# H01R0_Backend.net
KiCad netlist of a schematic drawn in Altium Designer
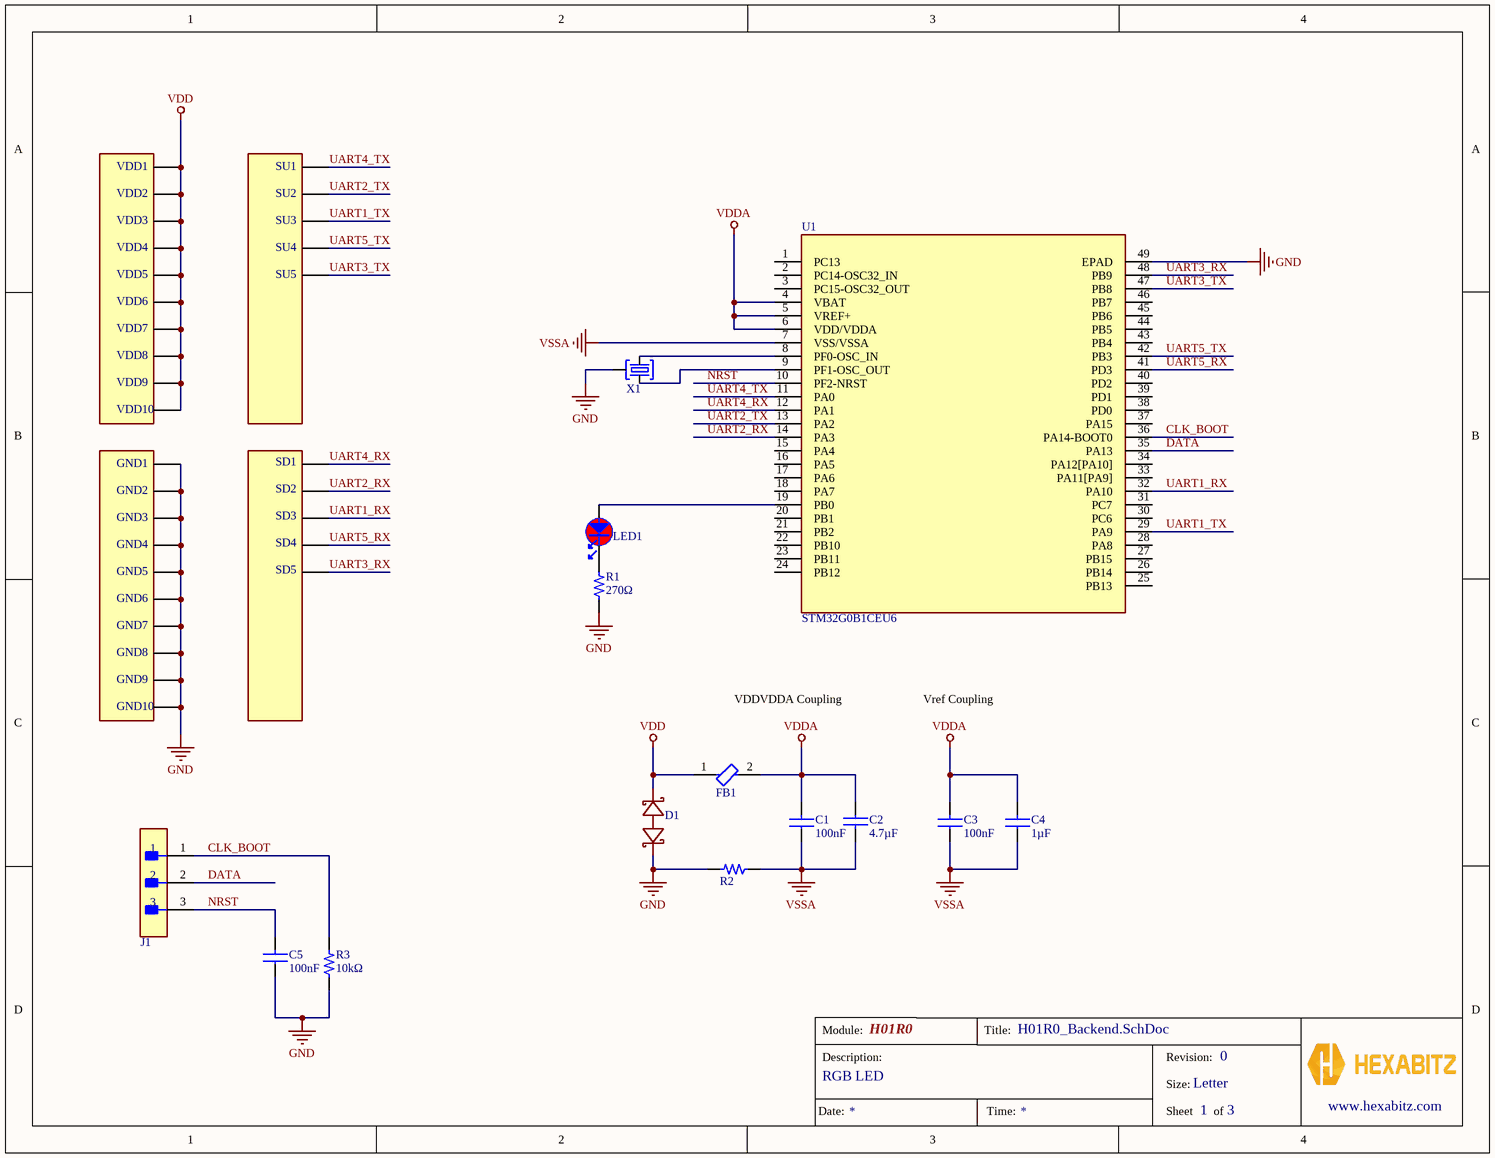
[diagram p0: H01R0_Backend.SchDoc]

(export (version "E")
  (design (tool "Eeschema 10.0.6"))
  (components
    (comp (ref "C1")
      (value "100nF")
      (footprint "C0603")
      (fields
        (field (name "MANUFACTURER") "Samsung Electro-Mechanics")
        (field (name "MANUFACTURER PART NUMBER") "CL10B104KA8NNNC")
        (field (name "TOLERANCE") "10%")
      )
      (libsource (lib "Hexabitz Altium Library") (part "generic Capacitor"))
    )
    (comp (ref "C2")
      (value "4.7µF")
      (footprint "C0805")
      (fields
        (field (name "MANUFACTURER") "Samsung Electro-Mechanics")
        (field (name "MANUFACTURER PART NUMBER") "CL21X475KAQNNNE")
        (field (name "TOLERANCE") "10%")
      )
      (libsource (lib "Hexabitz Altium Library") (part "generic Capacitor"))
    )
    (comp (ref "C3")
      (value "100nF")
      (footprint "C0603")
      (fields
        (field (name "MANUFACTURER") "Samsung Electro-Mechanics")
        (field (name "MANUFACTURER PART NUMBER") "CL10B104KA8NNNC")
        (field (name "TOLERANCE") "10%")
      )
      (libsource (lib "Hexabitz Altium Library") (part "generic Capacitor"))
    )
    (comp (ref "C4")
      (value "1µF")
      (footprint "C0805")
      (description "Ceramic Capacitor, Ceramic, 16V, 10% +Tol, 10% -Tol, X7R, 15% TC, 1uF, Surface Mount, 0805")
      (fields
        (field (name "MANUFACTURER") "Yageo Group")
        (field (name "MANUFACTURER PART NUMBER") "CC0805KKX7R7BB105")
      )
      (libsource (lib "Hexabitz Altium Library") (part "generic Capacitor"))
    )
    (comp (ref "C5")
      (value "100nF")
      (footprint "C0603")
      (fields
        (field (name "MANUFACTURER") "Samsung Electro-Mechanics")
        (field (name "MANUFACTURER PART NUMBER") "CL10B104KA8NNNC")
        (field (name "TOLERANCE") "10%")
      )
      (libsource (lib "Hexabitz Altium Library") (part "generic Capacitor"))
    )
    (comp (ref "D1")
      (value "CDSOD323-T03SC")
      (footprint "SOD2513X114N")
      (description "A 3V, 350W, bi-directional, standard capacitance, SOD323 pkg TVS Diode ¦ Bourns CDSOD323-T03SC")
      (fields (field (name "MANUFACTURER") "Bourns"))
      (libsource (lib "Hexabitz Altium Library") (part "CDSOD323-T03SC"))
    )
    (comp (ref "FB1")
      (value "MMZ1608Y300B")
      (footprint "FP-MMZ1608-0_8-MFG")
      (description "Ferrite Beads 0603 30ohms 1500mA Signal Line AEC-Q200")
      (fields
        (field (name "MANUFACTURER") "TDK")
        (field (name "MANUFACTURER PART NUMBER") "MMZ1608Y300BTD25")
      )
      (libsource (lib "Hexabitz Altium Library") (part "MMZ1608Y300B"))
    )
    (comp (ref "GND1")
      (value "HEXABIT_UART_PORT")
      (footprint "HEXABIT_POWER_PORT_D")
      (libsource (lib "hexabitz_connectors.Library") (part "HEXABIT_POWER_PORT_D"))
    )
    (comp (ref "GND2")
      (value "HEXABIT_UART_PORT")
      (footprint "HEXABIT_POWER_PORT_D")
      (libsource (lib "hexabitz_connectors.Library") (part "HEXABIT_POWER_PORT_D"))
    )
    (comp (ref "GND3")
      (value "HEXABIT_UART_PORT")
      (footprint "HEXABIT_POWER_PORT_D_300R")
      (libsource (lib "hexabitz_connectors.Library") (part "HEXABIT_POWER_PORT_D_300R"))
    )
    (comp (ref "GND4")
      (value "HEXABIT_UART_PORT")
      (footprint "HEXABIT_POWER_PORT_D")
      (libsource (lib "hexabitz_connectors.Library") (part "HEXABIT_POWER_PORT_D"))
    )
    (comp (ref "GND5")
      (value "HEXABIT_UART_PORT")
      (footprint "HEXABIT_POWER_PORT_D")
      (libsource (lib "hexabitz_connectors.Library") (part "HEXABIT_POWER_PORT_D"))
    )
    (comp (ref "GND6")
      (value "HEXABIT_UART_PORT")
      (footprint "HEXABIT_POWER_PORT_D")
      (libsource (lib "hexabitz_connectors.Library") (part "HEXABIT_POWER_PORT_D"))
    )
    (comp (ref "GND7")
      (value "HEXABIT_UART_PORT")
      (footprint "HEXABIT_POWER_PORT_D")
      (libsource (lib "hexabitz_connectors.Library") (part "HEXABIT_POWER_PORT_D"))
    )
    (comp (ref "GND8")
      (value "HEXABIT_UART_PORT")
      (footprint "HEXABIT_POWER_PORT_D_300L")
      (libsource (lib "hexabitz_connectors.Library") (part "HEXABIT_POWER_PORT_D_300L"))
    )
    (comp (ref "GND9")
      (value "HEXABIT_UART_PORT")
      (footprint "HEXABIT_POWER_PORT_D")
      (libsource (lib "hexabitz_connectors.Library") (part "HEXABIT_POWER_PORT_D"))
    )
    (comp (ref "GND10")
      (value "HEXABIT_UART_PORT")
      (footprint "HEXABIT_POWER_PORT_D")
      (libsource (lib "hexabitz_connectors.Library") (part "HEXABIT_POWER_PORT_D"))
    )
    (comp (ref "J1")
      (value "TSW-103-14-G-S")
      (footprint "FP-TSW-103-14-G-S-MFG")
      (description "CONN HEADER VERT 3POS 2.54MM")
      (libsource (lib "Altium Content Vault") (part "cd3439d6ef35ae5d9b27ec4fdd3e828"))
    )
    (comp (ref "LED1")
      (value "VLMS1300-GS08")
      (footprint "FP-6_541-5092_01-4-MFG")
      (description "LED Uni-Color Super Red 639nm 2-Pin Chip 0603(1608Metric) T/R")
      (fields (field (name "MANUFACTURER") "Vishay Semiconductors"))
      (libsource (lib "Hexabitz Altium Library") (part "VLMS1300-GS08"))
    )
    (comp (ref "R1")
      (value "270Ω")
      (footprint "R0603")
      (description "Res Thick Film 0603 270 Ohm 5% 0.1W(1/10W) ±200ppm/C Pad SMD Automotive T/R")
      (fields
        (field (name "MANUFACTURER") "Panasonic")
        (field (name "MANUFACTURER PART NUMBER") "ERJ-3GEYJ271V")
      )
      (libsource (lib "") (part "generic Resistor_2"))
    )
    (comp (ref "R2")
      (value "Manufacturer Part Number")
      (footprint "R0603")
      (libsource (lib "") (part "generic Resistor_1"))
    )
    (comp (ref "R3")
      (value "10kΩ")
      (footprint "R0603")
      (description "100mW Thick Film Resistors ±100ppm/℃ ±1% 10kΩ 0603 Chip Resistor - Surface Mount ROHS")
      (fields
        (field (name "MANUFACTURER") "Yageo Group")
        (field (name "MANUFACTURER PART NUMBER") "RC0603FR-0710KL")
      )
      (libsource (lib "Hexabitz Altium Library") (part "generic Resistor"))
    )
    (comp (ref "SD1")
      (value "HEXABIT_UART_PORT")
      (footprint "HEXABIT_UART_PORT_D")
      (libsource (lib "hexabitz_connectors.Library") (part "HEXABIT_UART_PORT_D"))
    )
    (comp (ref "SD2")
      (value "HEXABIT_UART_PORT")
      (footprint "HEXABIT_UART_PORT_D")
      (libsource (lib "hexabitz_connectors.Library") (part "HEXABIT_UART_PORT_D"))
    )
    (comp (ref "SD3")
      (value "HEXABIT_UART_PORT")
      (footprint "HEXABIT_UART_PORT_D")
      (libsource (lib "hexabitz_connectors.Library") (part "HEXABIT_UART_PORT_D"))
    )
    (comp (ref "SD4")
      (value "HEXABIT_UART_PORT")
      (footprint "HEXABIT_UART_PORT_D")
      (libsource (lib "hexabitz_connectors.Library") (part "HEXABIT_UART_PORT_D"))
    )
    (comp (ref "SD5")
      (value "HEXABIT_UART_PORT")
      (footprint "HEXABIT_UART_PORT_D")
      (libsource (lib "hexabitz_connectors.Library") (part "HEXABIT_UART_PORT_D"))
    )
    (comp (ref "SU1")
      (value "HEXABIT_UART_PORT")
      (footprint "HEXABIT_UART_PORT_U")
      (libsource (lib "hexabitz_connectors.Library") (part "HEXABIT_UART_PORT_U"))
    )
    (comp (ref "SU2")
      (value "HEXABIT_UART_PORT")
      (footprint "HEXABIT_UART_PORT_U")
      (libsource (lib "hexabitz_connectors.Library") (part "HEXABIT_UART_PORT_U"))
    )
    (comp (ref "SU3")
      (value "HEXABIT_UART_PORT")
      (footprint "HEXABIT_UART_PORT_U")
      (libsource (lib "hexabitz_connectors.Library") (part "HEXABIT_UART_PORT_U"))
    )
    (comp (ref "SU4")
      (value "HEXABIT_UART_PORT")
      (footprint "HEXABIT_UART_PORT_U")
      (libsource (lib "hexabitz_connectors.Library") (part "HEXABIT_UART_PORT_U"))
    )
    (comp (ref "SU5")
      (value "HEXABIT_UART_PORT")
      (footprint "HEXABIT_UART_PORT_U")
      (libsource (lib "hexabitz_connectors.Library") (part "HEXABIT_UART_PORT_U"))
    )
    (comp (ref "U1")
      (value "STM32G0B1CEU6")
      (footprint "QFN50P700X700X65-49N-D")
      (description "MCU 32-bit ARM Cortex M0+ RISC 512KB Flash 1.8V/2.5V/3.3V 48-Pin UFQFPN EP Tray")
      (fields
        (field (name "MANUFACTURER") "STMicroelectronics")
        (field (name "MANUFACTURER PART NUMBER") "STM32G0B1CEU6")
      )
      (libsource (lib "Hexabitz Altium Library") (part "STM32G0B1CEU6"))
    )
    (comp (ref "VDD1")
      (value "HEXABIT_UART_PORT")
      (footprint "HEXABIT_POWER_PORT_U")
      (libsource (lib "hexabitz_connectors.Library") (part "HEXABIT_POWER_PORT_U"))
    )
    (comp (ref "VDD2")
      (value "HEXABIT_UART_PORT")
      (footprint "HEXABIT_POWER_PORT_U")
      (libsource (lib "hexabitz_connectors.Library") (part "HEXABIT_POWER_PORT_U"))
    )
    (comp (ref "VDD3")
      (value "HEXABIT_UART_PORT")
      (footprint "HEXABIT_POWER_PORT_U_300R")
      (libsource (lib "hexabitz_connectors.Library") (part "HEXABIT_POWER_PORT_U_300R"))
    )
    (comp (ref "VDD4")
      (value "HEXABIT_UART_PORT")
      (footprint "HEXABIT_POWER_PORT_U")
      (libsource (lib "hexabitz_connectors.Library") (part "HEXABIT_POWER_PORT_U"))
    )
    (comp (ref "VDD5")
      (value "HEXABIT_UART_PORT")
      (footprint "HEXABIT_POWER_PORT_U")
      (libsource (lib "hexabitz_connectors.Library") (part "HEXABIT_POWER_PORT_U"))
    )
    (comp (ref "VDD6")
      (value "HEXABIT_UART_PORT")
      (footprint "HEXABIT_POWER_PORT_U")
      (libsource (lib "hexabitz_connectors.Library") (part "HEXABIT_POWER_PORT_U"))
    )
    (comp (ref "VDD7")
      (value "HEXABIT_UART_PORT")
      (footprint "HEXABIT_POWER_PORT_U")
      (libsource (lib "hexabitz_connectors.Library") (part "HEXABIT_POWER_PORT_U"))
    )
    (comp (ref "VDD8")
      (value "HEXABIT_UART_PORT")
      (footprint "HEXABIT_POWER_PORT_U_300L")
      (libsource (lib "hexabitz_connectors.Library") (part "HEXABIT_POWER_PORT_U_300L"))
    )
    (comp (ref "VDD9")
      (value "HEXABIT_UART_PORT")
      (footprint "HEXABIT_POWER_PORT_U")
      (libsource (lib "hexabitz_connectors.Library") (part "HEXABIT_POWER_PORT_U"))
    )
    (comp (ref "VDD10")
      (value "HEXABIT_UART_PORT")
      (footprint "HEXABIT_POWER_PORT_U")
      (libsource (lib "hexabitz_connectors.Library") (part "HEXABIT_POWER_PORT_U"))
    )
    (comp (ref "X1")
      (value "CSTCE8M00G52Z-R0")
      (footprint "XTALL_CSTCE8M00G52")
      (description "Ceramic Resonator 8MHz ±0.5% (Tol) ±0.2% (Stability) 10pF 40Ohm 3-Pin CSMD T/R")
      (fields (field (name "MANUFACTURER") "Murata") (field (name "TOLERANCE") "0.5%"))
      (libsource (lib "Hexabitz Altium Library") (part "CSTCE8M00G52Z-R0"))
    )
  )
  (nets
    (net (code "1") (name "/CLK_BOOT") (class "Default")
      (node (ref "J1") (pin "1") (pinfunction "1_1") (pintype "passive"))
      (node (ref "R3") (pin "1") (pinfunction "1_1") (pintype "passive"))
      (node (ref "U1") (pin "36") (pinfunction "PA14-BOOT0_36") (pintype "passive"))
    )
    (net (code "2") (name "/DATA") (class "Default")
      (node (ref "J1") (pin "2") (pinfunction "2_2") (pintype "passive"))
      (node (ref "U1") (pin "35") (pinfunction "PA13_35") (pintype "passive"))
    )
    (net (code "3") (name "/NRST") (class "Default")
      (node (ref "C5") (pin "2") (pinfunction "2_2") (pintype "passive"))
      (node (ref "J1") (pin "3") (pinfunction "3_3") (pintype "passive"))
      (node (ref "U1") (pin "10") (pinfunction "PF2-NRST_10") (pintype "passive"))
    )
    (net (code "4") (name "/UART1_RX") (class "Default")
      (node (ref "SD3") (pin "UART_D") (pinfunction "UART_D_UART_D") (pintype "passive"))
      (node (ref "U1") (pin "32") (pinfunction "PA10_32") (pintype "passive"))
    )
    (net (code "5") (name "/UART1_TX") (class "Default")
      (node (ref "SU3") (pin "UART_U") (pinfunction "UART_U_UART_U") (pintype "passive"))
      (node (ref "U1") (pin "29") (pinfunction "PA9_29") (pintype "passive"))
    )
    (net (code "6") (name "/UART2_RX") (class "Default")
      (node (ref "SD2") (pin "UART_D") (pinfunction "UART_D_UART_D") (pintype "passive"))
      (node (ref "U1") (pin "14") (pinfunction "PA3_14") (pintype "passive"))
    )
    (net (code "7") (name "/UART2_TX") (class "Default")
      (node (ref "SU2") (pin "UART_U") (pinfunction "UART_U_UART_U") (pintype "passive"))
      (node (ref "U1") (pin "13") (pinfunction "PA2_13") (pintype "passive"))
    )
    (net (code "8") (name "/UART3_RX") (class "Default")
      (node (ref "SD5") (pin "UART_D") (pinfunction "UART_D_UART_D") (pintype "passive"))
      (node (ref "U1") (pin "48") (pinfunction "PB9_48") (pintype "passive"))
    )
    (net (code "9") (name "/UART3_TX") (class "Default")
      (node (ref "SU5") (pin "UART_U") (pinfunction "UART_U_UART_U") (pintype "passive"))
      (node (ref "U1") (pin "47") (pinfunction "PB8_47") (pintype "passive"))
    )
    (net (code "10") (name "/UART4_RX") (class "Default")
      (node (ref "SD1") (pin "UART_D") (pinfunction "UART_D_UART_D") (pintype "passive"))
      (node (ref "U1") (pin "12") (pinfunction "PA1_12") (pintype "passive"))
    )
    (net (code "11") (name "/UART4_TX") (class "Default")
      (node (ref "SU1") (pin "UART_U") (pinfunction "UART_U_UART_U") (pintype "passive"))
      (node (ref "U1") (pin "11") (pinfunction "PA0_11") (pintype "passive"))
    )
    (net (code "12") (name "/UART5_RX") (class "Default")
      (node (ref "SD4") (pin "UART_D") (pinfunction "UART_D_UART_D") (pintype "passive"))
      (node (ref "U1") (pin "41") (pinfunction "PD3_41") (pintype "passive"))
    )
    (net (code "13") (name "/UART5_TX") (class "Default")
      (node (ref "SU4") (pin "UART_U") (pinfunction "UART_U_UART_U") (pintype "passive"))
      (node (ref "U1") (pin "42") (pinfunction "PB3_42") (pintype "passive"))
    )
    (net (code "14") (name "GND") (class "Default")
      (node (ref "C5") (pin "1") (pinfunction "1_1") (pintype "passive"))
      (node (ref "D1") (pin "1") (pinfunction "A_1") (pintype "passive"))
      (node (ref "GND1") (pin "Pwr_D") (pinfunction "Pwr_D_Pwr_D") (pintype "passive"))
      (node (ref "GND10") (pin "Pwr_D") (pinfunction "Pwr_D_Pwr_D") (pintype "passive"))
      (node (ref "GND2") (pin "Pwr_D") (pinfunction "Pwr_D_Pwr_D") (pintype "passive"))
      (node (ref "GND3") (pin "Pwr_D") (pinfunction "Pwr_D_Pwr_D") (pintype "passive"))
      (node (ref "GND4") (pin "Pwr_D") (pinfunction "Pwr_D_Pwr_D") (pintype "passive"))
      (node (ref "GND5") (pin "Pwr_D") (pinfunction "Pwr_D_Pwr_D") (pintype "passive"))
      (node (ref "GND6") (pin "Pwr_D") (pinfunction "Pwr_D_Pwr_D") (pintype "passive"))
      (node (ref "GND7") (pin "Pwr_D") (pinfunction "Pwr_D_Pwr_D") (pintype "passive"))
      (node (ref "GND8") (pin "Pwr_D") (pinfunction "Pwr_D_Pwr_D") (pintype "passive"))
      (node (ref "GND9") (pin "Pwr_D") (pinfunction "Pwr_D_Pwr_D") (pintype "passive"))
      (node (ref "R1") (pin "1") (pinfunction "1_1") (pintype "passive"))
      (node (ref "R2") (pin "1") (pinfunction "1_1") (pintype "passive"))
      (node (ref "R3") (pin "2") (pinfunction "2_2") (pintype "passive"))
      (node (ref "U1") (pin "49") (pinfunction "EPAD_49") (pintype "passive"))
      (node (ref "X1") (pin "P$2") (pinfunction "2_P$2") (pintype "passive"))
    )
    (net (code "15") (name "Net-(LED1-Pad1)") (class "Default")
      (node (ref "LED1") (pin "1") (pintype "passive"))
      (node (ref "R1") (pin "2") (pinfunction "2_2") (pintype "passive"))
    )
    (net (code "16") (name "Net-(U1-PB0)") (class "Default")
      (node (ref "LED1") (pin "2") (pintype "passive"))
      (node (ref "U1") (pin "19") (pinfunction "PB0_19") (pintype "passive"))
    )
    (net (code "17") (name "Net-(U1-PF0-OSC_IN)") (class "Default")
      (node (ref "U1") (pin "8") (pinfunction "PF0-OSC_IN_8") (pintype "passive"))
      (node (ref "X1") (pin "P$3") (pinfunction "3_P$3") (pintype "passive"))
    )
    (net (code "18") (name "Net-(U1-PF1-OSC_OUT)") (class "Default")
      (node (ref "U1") (pin "9") (pinfunction "PF1-OSC_OUT_9") (pintype "passive"))
      (node (ref "X1") (pin "P$1") (pinfunction "1_P$1") (pintype "passive"))
    )
    (net (code "19") (name "VDD") (class "Default")
      (node (ref "D1") (pin "2") (pinfunction "C_2") (pintype "passive"))
      (node (ref "FB1") (pin "1") (pinfunction "1_1") (pintype "passive"))
      (node (ref "VDD1") (pin "Pwr_U") (pinfunction "Pwr_U_Pwr_U") (pintype "passive"))
      (node (ref "VDD10") (pin "Pwr_U") (pinfunction "Pwr_U_Pwr_U") (pintype "passive"))
      (node (ref "VDD2") (pin "Pwr_U") (pinfunction "Pwr_U_Pwr_U") (pintype "passive"))
      (node (ref "VDD3") (pin "Pwr_U") (pinfunction "Pwr_U_Pwr_U") (pintype "passive"))
      (node (ref "VDD4") (pin "Pwr_U") (pinfunction "Pwr_U_Pwr_U") (pintype "passive"))
      (node (ref "VDD5") (pin "Pwr_U") (pinfunction "Pwr_U_Pwr_U") (pintype "passive"))
      (node (ref "VDD6") (pin "Pwr_U") (pinfunction "Pwr_U_Pwr_U") (pintype "passive"))
      (node (ref "VDD7") (pin "Pwr_U") (pinfunction "Pwr_U_Pwr_U") (pintype "passive"))
      (node (ref "VDD8") (pin "Pwr_U") (pinfunction "Pwr_U_Pwr_U") (pintype "passive"))
      (node (ref "VDD9") (pin "Pwr_U") (pinfunction "Pwr_U_Pwr_U") (pintype "passive"))
    )
    (net (code "20") (name "VDDA") (class "Default")
      (node (ref "C1") (pin "2") (pinfunction "2_2") (pintype "passive"))
      (node (ref "C2") (pin "1") (pinfunction "1_1") (pintype "passive"))
      (node (ref "C3") (pin "2") (pinfunction "2_2") (pintype "passive"))
      (node (ref "C4") (pin "2") (pinfunction "2_2") (pintype "passive"))
      (node (ref "FB1") (pin "2") (pinfunction "2_2") (pintype "passive"))
      (node (ref "U1") (pin "4") (pinfunction "VBAT_4") (pintype "passive"))
      (node (ref "U1") (pin "5") (pinfunction "VREF+_5") (pintype "passive"))
      (node (ref "U1") (pin "6") (pinfunction "VDD/VDDA_6") (pintype "passive"))
    )
    (net (code "21") (name "VSSA") (class "Default")
      (node (ref "C1") (pin "1") (pinfunction "1_1") (pintype "passive"))
      (node (ref "C2") (pin "2") (pinfunction "2_2") (pintype "passive"))
      (node (ref "C3") (pin "1") (pinfunction "1_1") (pintype "passive"))
      (node (ref "C4") (pin "1") (pinfunction "1_1") (pintype "passive"))
      (node (ref "R2") (pin "2") (pinfunction "2_2") (pintype "passive"))
      (node (ref "U1") (pin "7") (pinfunction "VSS/VSSA_7") (pintype "passive"))
    )
    (net (code "22") (name "unconnected-(U1-PA4-Pad15)") (class "Default")
      (node (ref "U1") (pin "15") (pinfunction "PA4_15") (pintype "passive"))
    )
    (net (code "23") (name "unconnected-(U1-PA5-Pad16)") (class "Default")
      (node (ref "U1") (pin "16") (pinfunction "PA5_16") (pintype "passive"))
    )
    (net (code "24") (name "unconnected-(U1-PA6-Pad17)") (class "Default")
      (node (ref "U1") (pin "17") (pinfunction "PA6_17") (pintype "passive"))
    )
    (net (code "25") (name "unconnected-(U1-PA7-Pad18)") (class "Default")
      (node (ref "U1") (pin "18") (pinfunction "PA7_18") (pintype "passive"))
    )
    (net (code "26") (name "unconnected-(U1-PA8-Pad28)") (class "Default")
      (node (ref "U1") (pin "28") (pinfunction "PA8_28") (pintype "passive"))
    )
    (net (code "27") (name "unconnected-(U1-PA11[PA9]-Pad33)") (class "Default")
      (node (ref "U1") (pin "33") (pinfunction "PA11[PA9]_33") (pintype "passive"))
    )
    (net (code "28") (name "unconnected-(U1-PA12[PA10]-Pad34)") (class "Default")
      (node (ref "U1") (pin "34") (pinfunction "PA12[PA10]_34") (pintype "passive"))
    )
    (net (code "29") (name "unconnected-(U1-PA15-Pad37)") (class "Default")
      (node (ref "U1") (pin "37") (pinfunction "PA15_37") (pintype "passive"))
    )
    (net (code "30") (name "unconnected-(U1-PB1-Pad20)") (class "Default")
      (node (ref "U1") (pin "20") (pinfunction "PB1_20") (pintype "passive"))
    )
    (net (code "31") (name "unconnected-(U1-PB2-Pad21)") (class "Default")
      (node (ref "U1") (pin "21") (pinfunction "PB2_21") (pintype "passive"))
    )
    (net (code "32") (name "unconnected-(U1-PB4-Pad43)") (class "Default")
      (node (ref "U1") (pin "43") (pinfunction "PB4_43") (pintype "passive"))
    )
    (net (code "33") (name "unconnected-(U1-PB5-Pad44)") (class "Default")
      (node (ref "U1") (pin "44") (pinfunction "PB5_44") (pintype "passive"))
    )
    (net (code "34") (name "unconnected-(U1-PB6-Pad45)") (class "Default")
      (node (ref "U1") (pin "45") (pinfunction "PB6_45") (pintype "passive"))
    )
    (net (code "35") (name "unconnected-(U1-PB7-Pad46)") (class "Default")
      (node (ref "U1") (pin "46") (pinfunction "PB7_46") (pintype "passive"))
    )
    (net (code "36") (name "unconnected-(U1-PB10-Pad22)") (class "Default")
      (node (ref "U1") (pin "22") (pinfunction "PB10_22") (pintype "passive"))
    )
    (net (code "37") (name "unconnected-(U1-PB11-Pad23)") (class "Default")
      (node (ref "U1") (pin "23") (pinfunction "PB11_23") (pintype "passive"))
    )
    (net (code "38") (name "unconnected-(U1-PB12-Pad24)") (class "Default")
      (node (ref "U1") (pin "24") (pinfunction "PB12_24") (pintype "passive"))
    )
    (net (code "39") (name "unconnected-(U1-PB13-Pad25)") (class "Default")
      (node (ref "U1") (pin "25") (pinfunction "PB13_25") (pintype "passive"))
    )
    (net (code "40") (name "unconnected-(U1-PB14-Pad26)") (class "Default")
      (node (ref "U1") (pin "26") (pinfunction "PB14_26") (pintype "passive"))
    )
    (net (code "41") (name "unconnected-(U1-PB15-Pad27)") (class "Default")
      (node (ref "U1") (pin "27") (pinfunction "PB15_27") (pintype "passive"))
    )
    (net (code "42") (name "unconnected-(U1-PC6-Pad30)") (class "Default")
      (node (ref "U1") (pin "30") (pinfunction "PC6_30") (pintype "passive"))
    )
    (net (code "43") (name "unconnected-(U1-PC7-Pad31)") (class "Default")
      (node (ref "U1") (pin "31") (pinfunction "PC7_31") (pintype "passive"))
    )
    (net (code "44") (name "unconnected-(U1-PC13-Pad1)") (class "Default")
      (node (ref "U1") (pin "1") (pinfunction "PC13_1") (pintype "passive"))
    )
    (net (code "45") (name "unconnected-(U1-PC14-OSC32_IN-Pad2)") (class "Default")
      (node (ref "U1") (pin "2") (pinfunction "PC14-OSC32_IN_2") (pintype "passive"))
    )
    (net (code "46") (name "unconnected-(U1-PC15-OSC32_OUT-Pad3)") (class "Default")
      (node (ref "U1") (pin "3") (pinfunction "PC15-OSC32_OUT_3") (pintype "passive"))
    )
    (net (code "47") (name "unconnected-(U1-PD0-Pad38)") (class "Default")
      (node (ref "U1") (pin "38") (pinfunction "PD0_38") (pintype "passive"))
    )
    (net (code "48") (name "unconnected-(U1-PD1-Pad39)") (class "Default")
      (node (ref "U1") (pin "39") (pinfunction "PD1_39") (pintype "passive"))
    )
    (net (code "49") (name "unconnected-(U1-PD2-Pad40)") (class "Default")
      (node (ref "U1") (pin "40") (pinfunction "PD2_40") (pintype "passive"))
    )
  )
)
